# 13_LCD_Backlight_Touchscreen.net
KiCad netlist of a schematic drawn in Altium Designer
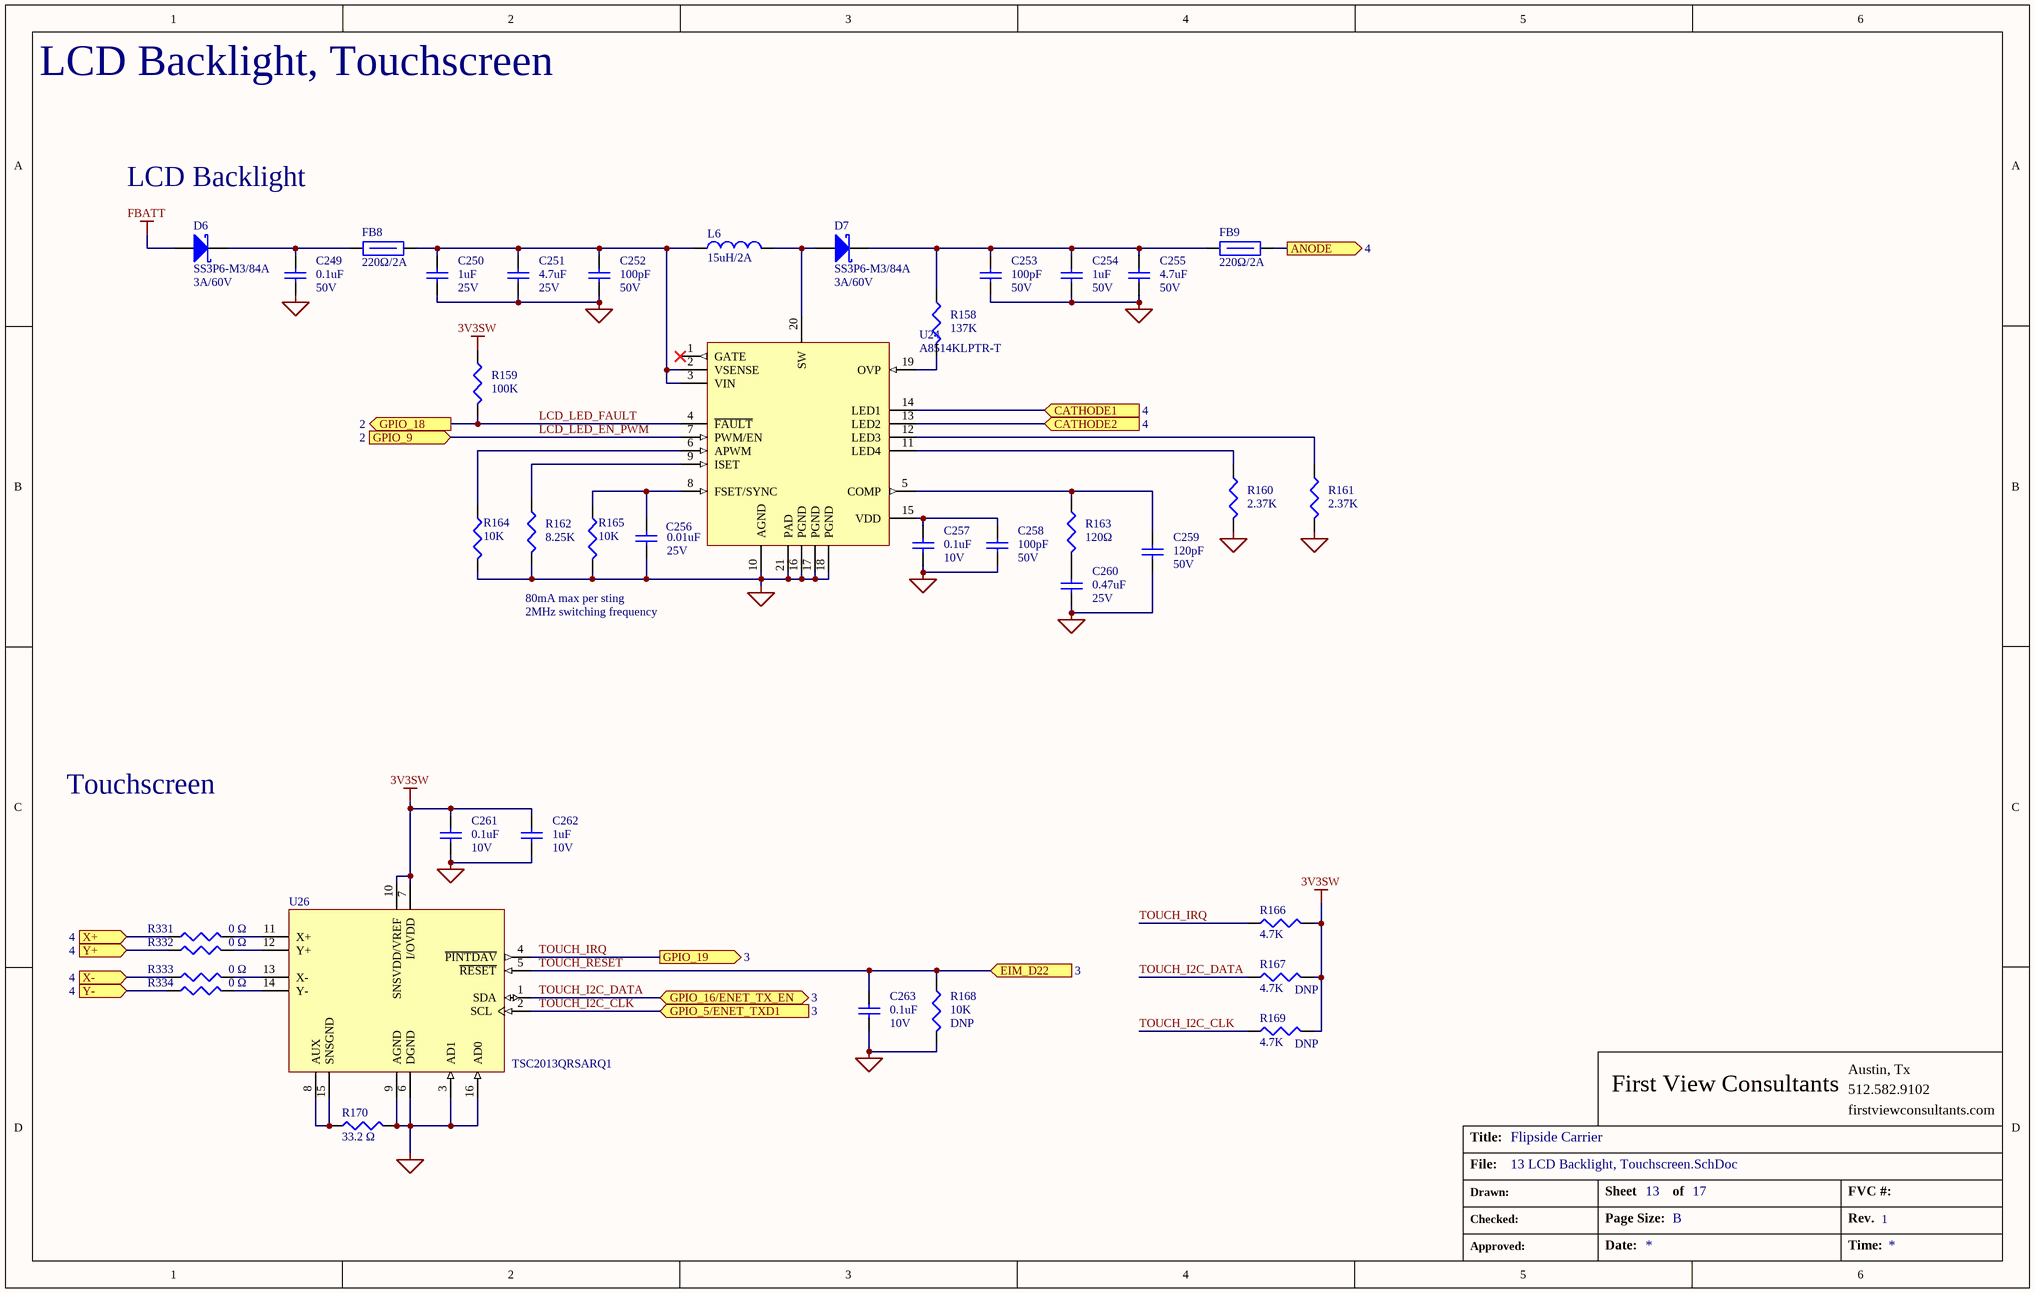
[diagram p0: 13 LCD Backlight, Touchscreen.SchDoc]

(export (version "E")
  (design (tool "Eeschema 10.0.6"))
  (components
    (comp (ref "C249")
      (value "0.1uF")
      (footprint "CAP_0402")
      (description "Cap, Cer, 0.1uF, 50V, 10%, X5R, 0402")
      (fields
        (field (name "TOLERANCE") "±10%")
        (field (name "MANUFACTURER") "TDK Corporation")
        (field (name "VOLTAGE") "50V")
      )
      (libsource (lib "Firstview") (part "Cap 0.1uF 50V 0402"))
    )
    (comp (ref "C250")
      (value "1uF")
      (footprint "CAP_0402")
      (description "Cap, Cer, 1uF, 25V, 10%, X5R, 0402")
      (fields
        (field (name "VOLTAGE") "25V")
        (field (name "MANUFACTURER") "Taiyo Yuden")
        (field (name "Comment") "Cap 1uF 25V 0402")
      )
      (libsource (lib "Firstview") (part "Cap 1uF 25V 0402"))
    )
    (comp (ref "C251")
      (value "4.7uF")
      (footprint "CAP_0805")
      (description "Cap, Cer, 4.7uF, 25V, 10%, X5R, 0805")
      (fields
        (field (name "TOLERANCE") "10%")
        (field (name "MANUFACTURER") "Murata Electronics North America")
        (field (name "VOLTAGE") "25V")
      )
      (libsource (lib "Firstview") (part "Cap 4.7uF 25V 0805"))
    )
    (comp (ref "C252")
      (value "100pF")
      (footprint "CAP_0402")
      (description "Cap, Cer, 100pF, 50V, 5%, C0G/NP0, 0402")
      (fields
        (field (name "TOLERANCE") "5%")
        (field (name "MANUFACTURER") "Yageo")
        (field (name "VOLTAGE") "50V")
      )
      (libsource (lib "Firstview") (part "Cap 100pF 50V 0402"))
    )
    (comp (ref "C253")
      (value "100pF")
      (footprint "CAP_0402")
      (description "Cap, Cer, 100pF, 50V, 5%, C0G/NP0, 0402")
      (fields
        (field (name "TOLERANCE") "5%")
        (field (name "MANUFACTURER") "Yageo")
        (field (name "VOLTAGE") "50V")
      )
      (libsource (lib "Firstview") (part "Cap 100pF 50V 0402"))
    )
    (comp (ref "C254")
      (value "1uF")
      (footprint "CAP_1206")
      (description "Cap, Cer, 1uF, 50V, 10%, X7R, 1206")
      (fields
        (field (name "MANUFACTURER") "Murata Electronics North America")
        (field (name "VOLTAGE") "50V")
        (field (name "Comment") "Cap 1uF 50V 1206")
      )
      (libsource (lib "Firstview") (part "Cap 1uF 50V 1206"))
    )
    (comp (ref "C255")
      (value "4.7uF")
      (footprint "CAP_1206")
      (description "Cap, Cer, 4.7uF, 50V, 10%, X7R, 1206")
      (fields
        (field (name "TOLERANCE") "10%")
        (field (name "MANUFACTURER") "Taiyo Yuden")
        (field (name "VOLTAGE") "50V")
      )
      (libsource (lib "Firstview") (part "Cap 4.7uF 50V 1206"))
    )
    (comp (ref "C256")
      (value "0.01uF")
      (footprint "CAP_0402")
      (description "Cap, Cer, 0.01uF, 25V, ±10%, X7R, 0402")
      (fields
        (field (name "TOLERANCE") "±10%")
        (field (name "MANUFACTURER") "Murata")
        (field (name "VOLTAGE") "25V")
      )
      (libsource (lib "Firstview") (part "Cap 0.01uF 50V 0402"))
    )
    (comp (ref "C257")
      (value "0.1uF")
      (footprint "CAP_0402")
      (description "Cap, Cer, 0.1uF, 10V, 10%, X5R, 0402")
      (fields
        (field (name "TOLERANCE") "±10%")
        (field (name "MANUFACTURER") "Murata Electronics North America")
        (field (name "VOLTAGE") "10V")
      )
      (libsource (lib "Firstview") (part "Cap 0.1uF 10V 0402"))
    )
    (comp (ref "C258")
      (value "100pF")
      (footprint "CAP_0402")
      (description "Cap, Cer, 100pF, 50V, 5%, C0G/NP0, 0402")
      (fields
        (field (name "TOLERANCE") "5%")
        (field (name "MANUFACTURER") "Yageo")
        (field (name "VOLTAGE") "50V")
      )
      (libsource (lib "Firstview") (part "Cap 100pF 50V 0402"))
    )
    (comp (ref "C259")
      (value "120pF")
      (footprint "CAP_0402")
      (description "Cap, Cer, 120pF, 50V, 5%, C0G/NP0, 0402")
      (fields
        (field (name "TOLERANCE") "5%")
        (field (name "MANUFACTURER") "Taiyo Yuden")
        (field (name "VOLTAGE") "50V")
      )
      (libsource (lib "Firstview") (part "Cap 120pF 50V 0402"))
    )
    (comp (ref "C260")
      (value "0.47uF")
      (footprint "CAP_0603")
      (description "Cap, Cer, 0.47uF, 25V, 10%, X7R, 0603")
      (fields
        (field (name "MANUFACTURER") "Samsung Electro-Mechanics America, Inc")
        (field (name "TOLERANCE") "10%")
        (field (name "VOLTAGE") "25V")
      )
      (libsource (lib "Firstview") (part "Cap 0.47uF 25V 0603"))
    )
    (comp (ref "C261")
      (value "0.1uF")
      (footprint "CAP_0402")
      (description "Cap, Cer, 0.1uF, 10V, 10%, X5R, 0402")
      (fields
        (field (name "TOLERANCE") "±10%")
        (field (name "MANUFACTURER") "Murata Electronics North America")
        (field (name "VOLTAGE") "10V")
      )
      (libsource (lib "Firstview") (part "Cap 0.1uF 10V 0402"))
    )
    (comp (ref "C262")
      (value "1uF")
      (footprint "CAP_0402")
      (description "Cap, Cer, 1uF, 10V, ±10%, X5R, 0402")
      (fields
        (field (name "VOLTAGE") "10V")
        (field (name "MANUFACTURER") "Yageo")
        (field (name "Comment") "Cap 1uF 10V 0402")
      )
      (libsource (lib "Firstview") (part "Cap 1uF 10V 0402"))
    )
    (comp (ref "C263")
      (value "0.1uF")
      (footprint "CAP_0402")
      (description "Cap, Cer, 0.1uF, 10V, 10%, X5R, 0402")
      (fields
        (field (name "TOLERANCE") "±10%")
        (field (name "MANUFACTURER") "Murata Electronics North America")
        (field (name "VOLTAGE") "10V")
      )
      (libsource (lib "Firstview") (part "Cap 0.1uF 10V 0402"))
    )
    (comp (ref "D6")
      (value "SS3P6-M3/84A")
      (footprint "DO-220AA_SS3P6-M3/84A")
      (description "Diode, Schottky, 3A, 60V, DO-220AA")
      (fields (field (name "MANUFACTURER") "Vishay") (field (name "ALTIUM_VALUE") "3A/60V"))
      (libsource (lib "Firstview") (part "SS3P6-M3/84A"))
    )
    (comp (ref "D7")
      (value "SS3P6-M3/84A")
      (footprint "DO-220AA_SS3P6-M3/84A")
      (description "Diode, Schottky, 3A, 60V, DO-220AA")
      (fields (field (name "MANUFACTURER") "Vishay") (field (name "ALTIUM_VALUE") "3A/60V"))
      (libsource (lib "Firstview") (part "SS3P6-M3/84A"))
    )
    (comp (ref "FB8")
      (value "220Ω/2A")
      (footprint "IND_0805")
      (description "Ind, Ferrite Bead, 220R, 50mOhm, 2A, 0805")
      (fields (field (name "MANUFACTURER") "Taiyo Yuden") (field (name "Comment") "BKP2125HS221-T"))
      (libsource (lib "Firstview") (part "BKP2125HS221-T"))
    )
    (comp (ref "FB9")
      (value "220Ω/2A")
      (footprint "IND_0805")
      (description "Ind, Ferrite Bead, 220R, 50mOhm, 2A, 0805")
      (fields (field (name "MANUFACTURER") "Taiyo Yuden") (field (name "Comment") "BKP2125HS221-T"))
      (libsource (lib "Firstview") (part "BKP2125HS221-T"))
    )
    (comp (ref "L6")
      (value "15uH/2A")
      (footprint "IND_NRS8030T150MJGJ")
      (description "Ind, Power, 15uH, 2A, 78mOhms, Shielded, SMD")
      (fields (field (name "MANUFACTURER") "Taiyo Yuden") (field (name "Comment") "NRS8030T150MJGJ"))
      (libsource (lib "Firstview") (part "NRS8030T150MJGJ"))
    )
    (comp (ref "R158")
      (value "137K")
      (footprint "RES_0402")
      (description "Res, 137K, 0.1W, 1%, 0402")
      (fields
        (field (name "MANUFACTURER") "Panasonic Electronic Components")
        (field (name "Comment") "Res 137K 0.1W")
      )
      (libsource (lib "Firstview") (part "Res 137K 0.1W"))
    )
    (comp (ref "R159")
      (value "100K")
      (footprint "RES_0402")
      (description "Res, 100K, 0.1W, 1%, 0402")
      (fields
        (field (name "MANUFACTURER") "Panasonic Electronic Components")
        (field (name "Comment") "Res 100K 0.1W")
      )
      (libsource (lib "Firstview") (part "Res 100K 0.1W"))
    )
    (comp (ref "R160")
      (value "2.37K")
      (footprint "RES_0402")
      (description "Res, 2.37K, 0.063W, 1%, 0402")
      (fields (field (name "MANUFACTURER") "Yageo") (field (name "Comment") "Res 2.37K 0.063W"))
      (libsource (lib "Firstview") (part "Res 2.37K 0.063W"))
    )
    (comp (ref "R161")
      (value "2.37K")
      (footprint "RES_0402")
      (description "Res, 2.37K, 0.063W, 1%, 0402")
      (fields (field (name "MANUFACTURER") "Yageo") (field (name "Comment") "Res 2.37K 0.063W"))
      (libsource (lib "Firstview") (part "Res 2.37K 0.063W"))
    )
    (comp (ref "R162")
      (value "8.25K")
      (footprint "RES_0402")
      (description "Res, 8.25K, 0.063W, 1%, 0402")
      (fields (field (name "MANUFACTURER") "Yageo") (field (name "Comment") "Res 8.25K 0.063W"))
      (libsource (lib "Firstview") (part "Res 8.25K 0.063W"))
    )
    (comp (ref "R163")
      (value "120Ω")
      (footprint "RES_0402")
      (description "Res, 120R, 0.063W, 1%, 0402")
      (fields (field (name "MANUFACTURER") "Rohm Semiconductor") (field (name "Comment") "Res 120R 0.063W"))
      (libsource (lib "Firstview") (part "Res 120R 0.063W"))
    )
    (comp (ref "R164")
      (value "10K")
      (footprint "RES_0402")
      (description "Res, 10K, 1/16W, 1%, 0402")
      (fields (field (name "MANUFACTURER") "Yageo") (field (name "Comment") "Res 10K 0.063W"))
      (libsource (lib "Firstview") (part "Res 10K 0.063W"))
    )
    (comp (ref "R165")
      (value "10K")
      (footprint "RES_0402")
      (description "Res, 10K, 1/16W, 1%, 0402")
      (fields (field (name "MANUFACTURER") "Yageo") (field (name "Comment") "Res 10K 0.063W"))
      (libsource (lib "Firstview") (part "Res 10K 0.063W"))
    )
    (comp (ref "R166")
      (value "4.7K")
      (footprint "RES_0402")
      (description "Res, 4.70K, 0.063W, 1%, 0402")
      (fields (field (name "MANUFACTURER") "Vishay Dale") (field (name "Comment") "Res 4.7K 0.063W"))
      (libsource (lib "Firstview") (part "Res 4.7K 0.063W"))
    )
    (comp (ref "R167")
      (value "4.7K")
      (footprint "RES_0402")
      (description "Res, 4.70K, 0.063W, 1%, 0402")
      (fields
        (field (name "DNP") "DNP")
        (field (name "MANUFACTURER") "Vishay Dale")
        (field (name "Comment") "Res 4.7K 0.063W")
      )
      (libsource (lib "Firstview") (part "Res 4.7K 0.063W"))
    )
    (comp (ref "R168")
      (value "10K")
      (footprint "RES_0402")
      (description "Res, 10K, 1/16W, 1%, 0402")
      (fields
        (field (name "DNP") "DNP")
        (field (name "MANUFACTURER") "Yageo")
        (field (name "Comment") "Res 10K 0.063W")
      )
      (libsource (lib "Firstview") (part "Res 10K 0.063W"))
    )
    (comp (ref "R169")
      (value "4.7K")
      (footprint "RES_0402")
      (description "Res, 4.70K, 0.063W, 1%, 0402")
      (fields
        (field (name "DNP") "DNP")
        (field (name "MANUFACTURER") "Vishay Dale")
        (field (name "Comment") "Res 4.7K 0.063W")
      )
      (libsource (lib "Firstview") (part "Res 4.7K 0.063W"))
    )
    (comp (ref "R170")
      (value "33.2 Ω")
      (footprint "RES_0402")
      (description "Res, 33.2R, 0.063W, 1%, 0402")
      (fields (field (name "MANUFACTURER") "Yageo") (field (name "Comment") "Res 33.2R 0.063W"))
      (libsource (lib "Firstview") (part "Res 33.2R 0.063W"))
    )
    (comp (ref "R331")
      (value "0 Ω")
      (footprint "RES_0402")
      (description "Res, 0 ohm, 1/16W, 0402")
      (fields (field (name "MANUFACTURER") "Vishay Dale") (field (name "Comment") "Res 0 ohm 0.1W"))
      (libsource (lib "Firstview") (part "Res 0 ohm 0.1W"))
    )
    (comp (ref "R332")
      (value "0 Ω")
      (footprint "RES_0402")
      (description "Res, 0 ohm, 1/16W, 0402")
      (fields (field (name "MANUFACTURER") "Vishay Dale") (field (name "Comment") "Res 0 ohm 0.1W"))
      (libsource (lib "Firstview") (part "Res 0 ohm 0.1W"))
    )
    (comp (ref "R333")
      (value "0 Ω")
      (footprint "RES_0402")
      (description "Res, 0 ohm, 1/16W, 0402")
      (fields (field (name "MANUFACTURER") "Vishay Dale") (field (name "Comment") "Res 0 ohm 0.1W"))
      (libsource (lib "Firstview") (part "Res 0 ohm 0.1W"))
    )
    (comp (ref "R334")
      (value "0 Ω")
      (footprint "RES_0402")
      (description "Res, 0 ohm, 1/16W, 0402")
      (fields (field (name "MANUFACTURER") "Vishay Dale") (field (name "Comment") "Res 0 ohm 0.1W"))
      (libsource (lib "Firstview") (part "Res 0 ohm 0.1W"))
    )
    (comp (ref "U24")
      (value "A8514KLPTR-T")
      (footprint "TSSOP-20_A8514KLPTR-T")
      (description "IC, LED Driver, 5-40V, PWM 580k-2.3MHz, TSSOP-20")
      (fields (field (name "MANUFACTURER") "Allegro"))
      (libsource (lib "Firstview") (part "A8514KLPTR-T"))
    )
    (comp (ref "U26")
      (value "TSC2013QRSARQ1")
      (footprint "QFN-16_TSC2013QRSARQ1")
      (description "IC, TS Controller, I2C, 12-bit, 4-wire, 1.6-3.6V, QFN-16")
      (fields (field (name "MANUFACTURER") "Texas Instruments"))
      (libsource (lib "Firstview") (part "TSC2013QRSARQ1"))
    )
  )
  (nets
    (net (code "1") (name "/ANODE") (class "Default")
      (node (ref "FB9") (pin "2") (pinfunction "2_2") (pintype "passive"))
    )
    (net (code "2") (name "/CATHODE1") (class "Default")
      (node (ref "U24") (pin "14") (pinfunction "LED1_14") (pintype "passive"))
    )
    (net (code "3") (name "/CATHODE2") (class "Default")
      (node (ref "U24") (pin "13") (pinfunction "LED2_13") (pintype "passive"))
    )
    (net (code "4") (name "/LCD_LED_EN_PWM") (class "Default")
      (node (ref "U24") (pin "7") (pinfunction "PWM/EN_7") (pintype "input"))
    )
    (net (code "5") (name "/LCD_LED_FAULT") (class "Default")
      (node (ref "R159") (pin "2") (pinfunction "2_2") (pintype "passive"))
      (node (ref "U24") (pin "4") (pinfunction "~{FAULT}_4") (pintype "passive"))
    )
    (net (code "6") (name "/TOUCH_I2C_CLK") (class "Default")
      (node (ref "R169") (pin "1") (pinfunction "1_1") (pintype "passive"))
      (node (ref "U26") (pin "2") (pinfunction "SCL_2") (pintype "input"))
    )
    (net (code "7") (name "/TOUCH_I2C_DATA") (class "Default")
      (node (ref "R167") (pin "1") (pinfunction "1_1") (pintype "passive"))
      (node (ref "U26") (pin "1") (pinfunction "SDA_1") (pintype "bidirectional"))
    )
    (net (code "8") (name "/TOUCH_IRQ") (class "Default")
      (node (ref "R166") (pin "1") (pinfunction "1_1") (pintype "passive"))
      (node (ref "U26") (pin "4") (pinfunction "~{PINTDAV}_4") (pintype "output"))
    )
    (net (code "9") (name "/TOUCH_RESET") (class "Default")
      (node (ref "C263") (pin "1") (pinfunction "1_1") (pintype "passive"))
      (node (ref "R168") (pin "1") (pinfunction "1_1") (pintype "passive"))
      (node (ref "U26") (pin "5") (pinfunction "~{RESET}_5") (pintype "input"))
    )
    (net (code "10") (name "/X+") (class "Default")
      (node (ref "R331") (pin "1") (pinfunction "1_1") (pintype "passive"))
    )
    (net (code "11") (name "/X-") (class "Default")
      (node (ref "R333") (pin "1") (pinfunction "1_1") (pintype "passive"))
    )
    (net (code "12") (name "/Y+") (class "Default")
      (node (ref "R332") (pin "1") (pinfunction "1_1") (pintype "passive"))
    )
    (net (code "13") (name "/Y-") (class "Default")
      (node (ref "R334") (pin "1") (pinfunction "1_1") (pintype "passive"))
    )
    (net (code "14") (name "3V3SW") (class "Default")
      (node (ref "C261") (pin "1") (pinfunction "1_1") (pintype "passive"))
      (node (ref "C262") (pin "1") (pinfunction "1_1") (pintype "passive"))
      (node (ref "R159") (pin "1") (pinfunction "1_1") (pintype "passive"))
      (node (ref "R166") (pin "2") (pinfunction "2_2") (pintype "passive"))
      (node (ref "R167") (pin "2") (pinfunction "2_2") (pintype "passive"))
      (node (ref "R169") (pin "2") (pinfunction "2_2") (pintype "passive"))
      (node (ref "U26") (pin "10") (pinfunction "SNSVDD/VREF_10") (pintype "passive"))
      (node (ref "U26") (pin "7") (pinfunction "I/OVDD_7") (pintype "power_in"))
    )
    (net (code "15") (name "FBATT") (class "Default")
      (node (ref "D6") (pin "A") (pinfunction "A_A") (pintype "passive"))
    )
    (net (code "16") (name "GND") (class "Default")
      (node (ref "C249") (pin "2") (pinfunction "2_2") (pintype "passive"))
      (node (ref "C250") (pin "2") (pinfunction "2_2") (pintype "passive"))
      (node (ref "C251") (pin "2") (pinfunction "2_2") (pintype "passive"))
      (node (ref "C252") (pin "2") (pinfunction "2_2") (pintype "passive"))
      (node (ref "C253") (pin "2") (pinfunction "2_2") (pintype "passive"))
      (node (ref "C254") (pin "2") (pinfunction "2_2") (pintype "passive"))
      (node (ref "C255") (pin "2") (pinfunction "2_2") (pintype "passive"))
      (node (ref "C256") (pin "2") (pinfunction "2_2") (pintype "passive"))
      (node (ref "C257") (pin "2") (pinfunction "2_2") (pintype "passive"))
      (node (ref "C258") (pin "2") (pinfunction "2_2") (pintype "passive"))
      (node (ref "C259") (pin "2") (pinfunction "2_2") (pintype "passive"))
      (node (ref "C260") (pin "2") (pinfunction "2_2") (pintype "passive"))
      (node (ref "C261") (pin "2") (pinfunction "2_2") (pintype "passive"))
      (node (ref "C262") (pin "2") (pinfunction "2_2") (pintype "passive"))
      (node (ref "C263") (pin "2") (pinfunction "2_2") (pintype "passive"))
      (node (ref "R160") (pin "2") (pinfunction "2_2") (pintype "passive"))
      (node (ref "R161") (pin "2") (pinfunction "2_2") (pintype "passive"))
      (node (ref "R162") (pin "2") (pinfunction "2_2") (pintype "passive"))
      (node (ref "R164") (pin "2") (pinfunction "2_2") (pintype "passive"))
      (node (ref "R165") (pin "2") (pinfunction "2_2") (pintype "passive"))
      (node (ref "R168") (pin "2") (pinfunction "2_2") (pintype "passive"))
      (node (ref "R170") (pin "2") (pinfunction "2_2") (pintype "passive"))
      (node (ref "U24") (pin "10") (pinfunction "AGND_10") (pintype "power_in"))
      (node (ref "U24") (pin "16") (pinfunction "PGND_16") (pintype "power_in"))
      (node (ref "U24") (pin "17") (pinfunction "PGND_17") (pintype "power_in"))
      (node (ref "U24") (pin "18") (pinfunction "PGND_18") (pintype "power_in"))
      (node (ref "U24") (pin "21") (pinfunction "PAD_21") (pintype "power_in"))
      (node (ref "U26") (pin "16") (pinfunction "AD0_16") (pintype "input"))
      (node (ref "U26") (pin "3") (pinfunction "AD1_3") (pintype "input"))
      (node (ref "U26") (pin "6") (pinfunction "DGND_6") (pintype "power_in"))
      (node (ref "U26") (pin "9") (pinfunction "AGND_9") (pintype "power_in"))
    )
    (net (code "17") (name "Net-(C249-Pad1)") (class "Default")
      (node (ref "C249") (pin "1") (pinfunction "1_1") (pintype "passive"))
      (node (ref "D6") (pin "K") (pinfunction "K_K") (pintype "passive"))
      (node (ref "FB8") (pin "1") (pinfunction "1_1") (pintype "passive"))
    )
    (net (code "18") (name "Net-(C253-Pad1)") (class "Default")
      (node (ref "C253") (pin "1") (pinfunction "1_1") (pintype "passive"))
      (node (ref "C254") (pin "1") (pinfunction "1_1") (pintype "passive"))
      (node (ref "C255") (pin "1") (pinfunction "1_1") (pintype "passive"))
      (node (ref "D7") (pin "K") (pinfunction "K_K") (pintype "passive"))
      (node (ref "FB9") (pin "1") (pinfunction "1_1") (pintype "passive"))
      (node (ref "R158") (pin "1") (pinfunction "1_1") (pintype "passive"))
    )
    (net (code "19") (name "Net-(C260-Pad1)") (class "Default")
      (node (ref "C260") (pin "1") (pinfunction "1_1") (pintype "passive"))
      (node (ref "R163") (pin "2") (pinfunction "2_2") (pintype "passive"))
    )
    (net (code "20") (name "Net-(U24-APWM)") (class "Default")
      (node (ref "R164") (pin "1") (pinfunction "1_1") (pintype "passive"))
      (node (ref "U24") (pin "6") (pinfunction "APWM_6") (pintype "input"))
    )
    (net (code "21") (name "Net-(U24-COMP)") (class "Default")
      (node (ref "C259") (pin "1") (pinfunction "1_1") (pintype "passive"))
      (node (ref "R163") (pin "1") (pinfunction "1_1") (pintype "passive"))
      (node (ref "U24") (pin "5") (pinfunction "COMP_5") (pintype "output"))
    )
    (net (code "22") (name "Net-(U24-FSET{slash}SYNC)") (class "Default")
      (node (ref "C256") (pin "1") (pinfunction "1_1") (pintype "passive"))
      (node (ref "R165") (pin "1") (pinfunction "1_1") (pintype "passive"))
      (node (ref "U24") (pin "8") (pinfunction "FSET/SYNC_8") (pintype "input"))
    )
    (net (code "23") (name "Net-(U24-ISET)") (class "Default")
      (node (ref "R162") (pin "1") (pinfunction "1_1") (pintype "passive"))
      (node (ref "U24") (pin "9") (pinfunction "ISET_9") (pintype "input"))
    )
    (net (code "24") (name "Net-(U24-LED3)") (class "Default")
      (node (ref "R161") (pin "1") (pinfunction "1_1") (pintype "passive"))
      (node (ref "U24") (pin "12") (pinfunction "LED3_12") (pintype "passive"))
    )
    (net (code "25") (name "Net-(U24-LED4)") (class "Default")
      (node (ref "R160") (pin "1") (pinfunction "1_1") (pintype "passive"))
      (node (ref "U24") (pin "11") (pinfunction "LED4_11") (pintype "passive"))
    )
    (net (code "26") (name "Net-(U24-OVP)") (class "Default")
      (node (ref "R158") (pin "2") (pinfunction "2_2") (pintype "passive"))
      (node (ref "U24") (pin "19") (pinfunction "OVP_19") (pintype "input"))
    )
    (net (code "27") (name "Net-(U24-SW)") (class "Default")
      (node (ref "D7") (pin "A") (pinfunction "A_A") (pintype "passive"))
      (node (ref "L6") (pin "2") (pinfunction "2_2") (pintype "passive"))
      (node (ref "U24") (pin "20") (pinfunction "SW_20") (pintype "passive"))
    )
    (net (code "28") (name "Net-(U24-VDD)") (class "Default")
      (node (ref "C257") (pin "1") (pinfunction "1_1") (pintype "passive"))
      (node (ref "C258") (pin "1") (pinfunction "1_1") (pintype "passive"))
      (node (ref "U24") (pin "15") (pinfunction "VDD_15") (pintype "power_in"))
    )
    (net (code "29") (name "Net-(U24-VIN)") (class "Default")
      (node (ref "C250") (pin "1") (pinfunction "1_1") (pintype "passive"))
      (node (ref "C251") (pin "1") (pinfunction "1_1") (pintype "passive"))
      (node (ref "C252") (pin "1") (pinfunction "1_1") (pintype "passive"))
      (node (ref "FB8") (pin "2") (pinfunction "2_2") (pintype "passive"))
      (node (ref "L6") (pin "1") (pinfunction "1_1") (pintype "passive"))
      (node (ref "U24") (pin "2") (pinfunction "VSENSE_2") (pintype "passive"))
      (node (ref "U24") (pin "3") (pinfunction "VIN_3") (pintype "power_in"))
    )
    (net (code "30") (name "Net-(U26-AUX)") (class "Default")
      (node (ref "R170") (pin "1") (pinfunction "1_1") (pintype "passive"))
      (node (ref "U26") (pin "15") (pinfunction "SNSGND_15") (pintype "power_in"))
      (node (ref "U26") (pin "8") (pinfunction "AUX_8") (pintype "passive"))
    )
    (net (code "31") (name "Net-(U26-X+)") (class "Default")
      (node (ref "R331") (pin "2") (pinfunction "2_2") (pintype "passive"))
      (node (ref "U26") (pin "11") (pinfunction "X+_11") (pintype "passive"))
    )
    (net (code "32") (name "Net-(U26-X-)") (class "Default")
      (node (ref "R333") (pin "2") (pinfunction "2_2") (pintype "passive"))
      (node (ref "U26") (pin "13") (pinfunction "X-_13") (pintype "passive"))
    )
    (net (code "33") (name "Net-(U26-Y+)") (class "Default")
      (node (ref "R332") (pin "2") (pinfunction "2_2") (pintype "passive"))
      (node (ref "U26") (pin "12") (pinfunction "Y+_12") (pintype "passive"))
    )
    (net (code "34") (name "Net-(U26-Y-)") (class "Default")
      (node (ref "R334") (pin "2") (pinfunction "2_2") (pintype "passive"))
      (node (ref "U26") (pin "14") (pinfunction "Y-_14") (pintype "passive"))
    )
    (net (code "35") (name "unconnected-(U24-GATE-Pad1)") (class "Default")
      (node (ref "U24") (pin "1") (pinfunction "GATE_1") (pintype "output+no_connect"))
    )
  )
)
